# IMU.net
KiCad netlist of a schematic drawn in Altium Designer
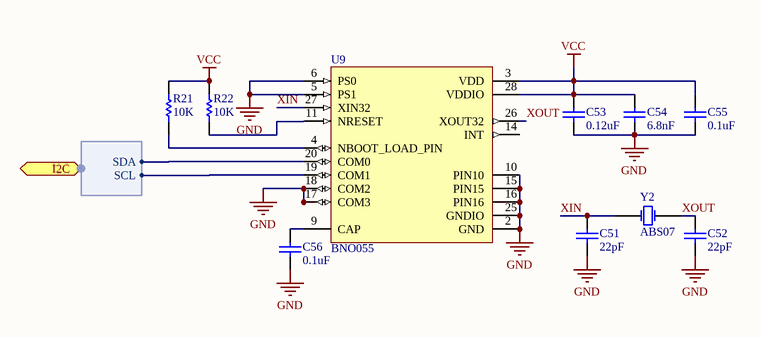
[diagram p0: IMU.SchDoc]

(export (version "E")
  (design (tool "Eeschema 10.0.6"))
  (components
    (comp (ref "C51")
      (value "22pF")
      (footprint "C0402[1005X55]")
      (description "22pF 50V 1% 0402 (1005 Metric)")
      (fields (field (name "TOLERANCE") "1%") (field (name "PARTNUMBER") "GRM1555C1H220FA01D"))
      (libsource (lib "Capacitors") (part "CAP_22pF_50V_0402_1%"))
    )
    (comp (ref "C52")
      (value "22pF")
      (footprint "C0402[1005X55]")
      (description "22pF 50V 1% 0402 (1005 Metric)")
      (fields (field (name "TOLERANCE") "1%") (field (name "PARTNUMBER") "GRM1555C1H220FA01D"))
      (libsource (lib "Capacitors") (part "CAP_22pF_50V_0402_1%"))
    )
    (comp (ref "C53")
      (value "0.12uF")
      (footprint "C0402[1005X55]")
      (description "0.12uF 6.3V 10% 0402 (1005 Metric)")
      (fields (field (name "TOLERANCE") "10%") (field (name "PARTNUMBER") "GRM155R60J124KE01D"))
      (libsource (lib "Capacitors") (part "CAP_0.12uF_6.3V_0402_10%"))
    )
    (comp (ref "C54")
      (value "6.8nF")
      (footprint "C0402[1005X55]")
      (description "6.8nF 50V 10% 0402 (1005 Metric)")
      (fields (field (name "TOLERANCE") "10%") (field (name "PARTNUMBER") "GRM155R71H682KA88J"))
      (libsource (lib "Capacitors") (part "CAP_6.8nF_50V_0402_10%"))
    )
    (comp (ref "C55")
      (value "0.1uF")
      (footprint "C0402[1005X55]")
      (description "0.1uF 6.3V 10% 0402 (1005 Metric)")
      (fields (field (name "TOLERANCE") "10%") (field (name "PARTNUMBER") "GRM155R70J104KA01D"))
      (libsource (lib "Capacitors") (part "CAP_0.1uF_6.3V_0402_10%"))
    )
    (comp (ref "C56")
      (value "0.1uF")
      (footprint "C0402[1005X55]")
      (description "0.1uF 6.3V 10% 0402 (1005 Metric)")
      (fields (field (name "TOLERANCE") "10%") (field (name "PARTNUMBER") "GRM155R70J104KA01D"))
      (libsource (lib "Capacitors") (part "CAP_0.1uF_6.3V_0402_10%"))
    )
    (comp (ref "R21")
      (value "10K")
      (footprint "R0402[1005]")
      (description "10K 0.063W 1% 0402 (1005 Metric)")
      (fields (field (name "TOLERANCE") "1%") (field (name "POWER") "0.063W"))
      (libsource (lib "Resistors") (part "RES_10K_0402_1%"))
    )
    (comp (ref "R22")
      (value "10K")
      (footprint "R0402[1005]")
      (description "10K 0.063W 1% 0402 (1005 Metric)")
      (fields (field (name "TOLERANCE") "1%") (field (name "POWER") "0.063W"))
      (libsource (lib "Resistors") (part "RES_10K_0402_1%"))
    )
    (comp (ref "U9")
      (value "BNO055")
      (footprint "LGA28R50P4X10_380X520X100")
      (libsource (lib "Components") (part "BNO055"))
    )
    (comp (ref "Y2")
      (value "ABS07")
      (footprint "ABS07")
      (fields (field (name "MANUFACTURER") "Abracon") (field (name "PARTNUMBER") "ABS07-32.768KHZ-T"))
      (libsource (lib "Components") (part "ABS07"))
    )
  )
  (nets
    (net (code "2") (name "/SCL") (class "Default")
      (node (ref "U9") (pin "19") (pinfunction "COM1_19") (pintype "bidirectional"))
    )
    (net (code "3") (name "/SDA") (class "Default")
      (node (ref "U9") (pin "20") (pinfunction "COM0_20") (pintype "bidirectional"))
    )
    (net (code "4") (name "/XIN") (class "Default")
      (node (ref "C51") (pin "2") (pinfunction "2_2") (pintype "passive"))
      (node (ref "U9") (pin "27") (pinfunction "XIN32_27") (pintype "input"))
      (node (ref "Y2") (pin "1") (pinfunction "X1_1") (pintype "passive"))
    )
    (net (code "5") (name "/XOUT") (class "Default")
      (node (ref "C52") (pin "2") (pinfunction "2_2") (pintype "passive"))
      (node (ref "U9") (pin "26") (pinfunction "XOUT32_26") (pintype "output"))
      (node (ref "Y2") (pin "2") (pinfunction "X2_2") (pintype "passive"))
    )
    (net (code "7") (name "GND") (class "Default")
      (node (ref "C51") (pin "1") (pinfunction "1_1") (pintype "passive"))
      (node (ref "C52") (pin "1") (pinfunction "1_1") (pintype "passive"))
      (node (ref "C53") (pin "1") (pinfunction "1_1") (pintype "passive"))
      (node (ref "C54") (pin "1") (pinfunction "1_1") (pintype "passive"))
      (node (ref "C55") (pin "1") (pinfunction "1_1") (pintype "passive"))
      (node (ref "C56") (pin "1") (pinfunction "1_1") (pintype "passive"))
      (node (ref "U9") (pin "10") (pinfunction "PIN10_10") (pintype "power_in"))
      (node (ref "U9") (pin "15") (pinfunction "PIN15_15") (pintype "power_in"))
      (node (ref "U9") (pin "16") (pinfunction "PIN16_16") (pintype "power_in"))
      (node (ref "U9") (pin "17") (pinfunction "COM3_17") (pintype "bidirectional"))
      (node (ref "U9") (pin "18") (pinfunction "COM2_18") (pintype "bidirectional"))
      (node (ref "U9") (pin "2") (pinfunction "GND_2") (pintype "power_in"))
      (node (ref "U9") (pin "25") (pinfunction "GNDIO_25") (pintype "power_in"))
      (node (ref "U9") (pin "5") (pinfunction "PS1_5") (pintype "input"))
      (node (ref "U9") (pin "6") (pinfunction "PS0_6") (pintype "input"))
    )
    (net (code "8") (name "Net-(U9-CAP)") (class "Default")
      (node (ref "C56") (pin "2") (pinfunction "2_2") (pintype "passive"))
      (node (ref "U9") (pin "9") (pinfunction "CAP_9") (pintype "passive"))
    )
    (net (code "9") (name "Net-(U9-NBOOT_LOAD_PIN)") (class "Default")
      (node (ref "R21") (pin "1") (pinfunction "1_1") (pintype "passive"))
      (node (ref "U9") (pin "4") (pinfunction "NBOOT_LOAD_PIN_4") (pintype "bidirectional"))
    )
    (net (code "10") (name "Net-(U9-NRESET)") (class "Default")
      (node (ref "R22") (pin "1") (pinfunction "1_1") (pintype "passive"))
      (node (ref "U9") (pin "11") (pinfunction "NRESET_11") (pintype "input"))
    )
    (net (code "11") (name "VCC") (class "Default")
      (node (ref "C53") (pin "2") (pinfunction "2_2") (pintype "passive"))
      (node (ref "C54") (pin "2") (pinfunction "2_2") (pintype "passive"))
      (node (ref "C55") (pin "2") (pinfunction "2_2") (pintype "passive"))
      (node (ref "R21") (pin "2") (pinfunction "2_2") (pintype "passive"))
      (node (ref "R22") (pin "2") (pinfunction "2_2") (pintype "passive"))
      (node (ref "U9") (pin "28") (pinfunction "VDDIO_28") (pintype "power_in"))
      (node (ref "U9") (pin "3") (pinfunction "VDD_3") (pintype "power_in"))
    )
    (net (code "12") (name "unconnected-(U9-INT-Pad14)") (class "Default")
      (node (ref "U9") (pin "14") (pinfunction "INT_14") (pintype "output"))
    )
  )
)
